# 18F_Proto2.net
KiCad netlist of a schematic drawn in EAGLE
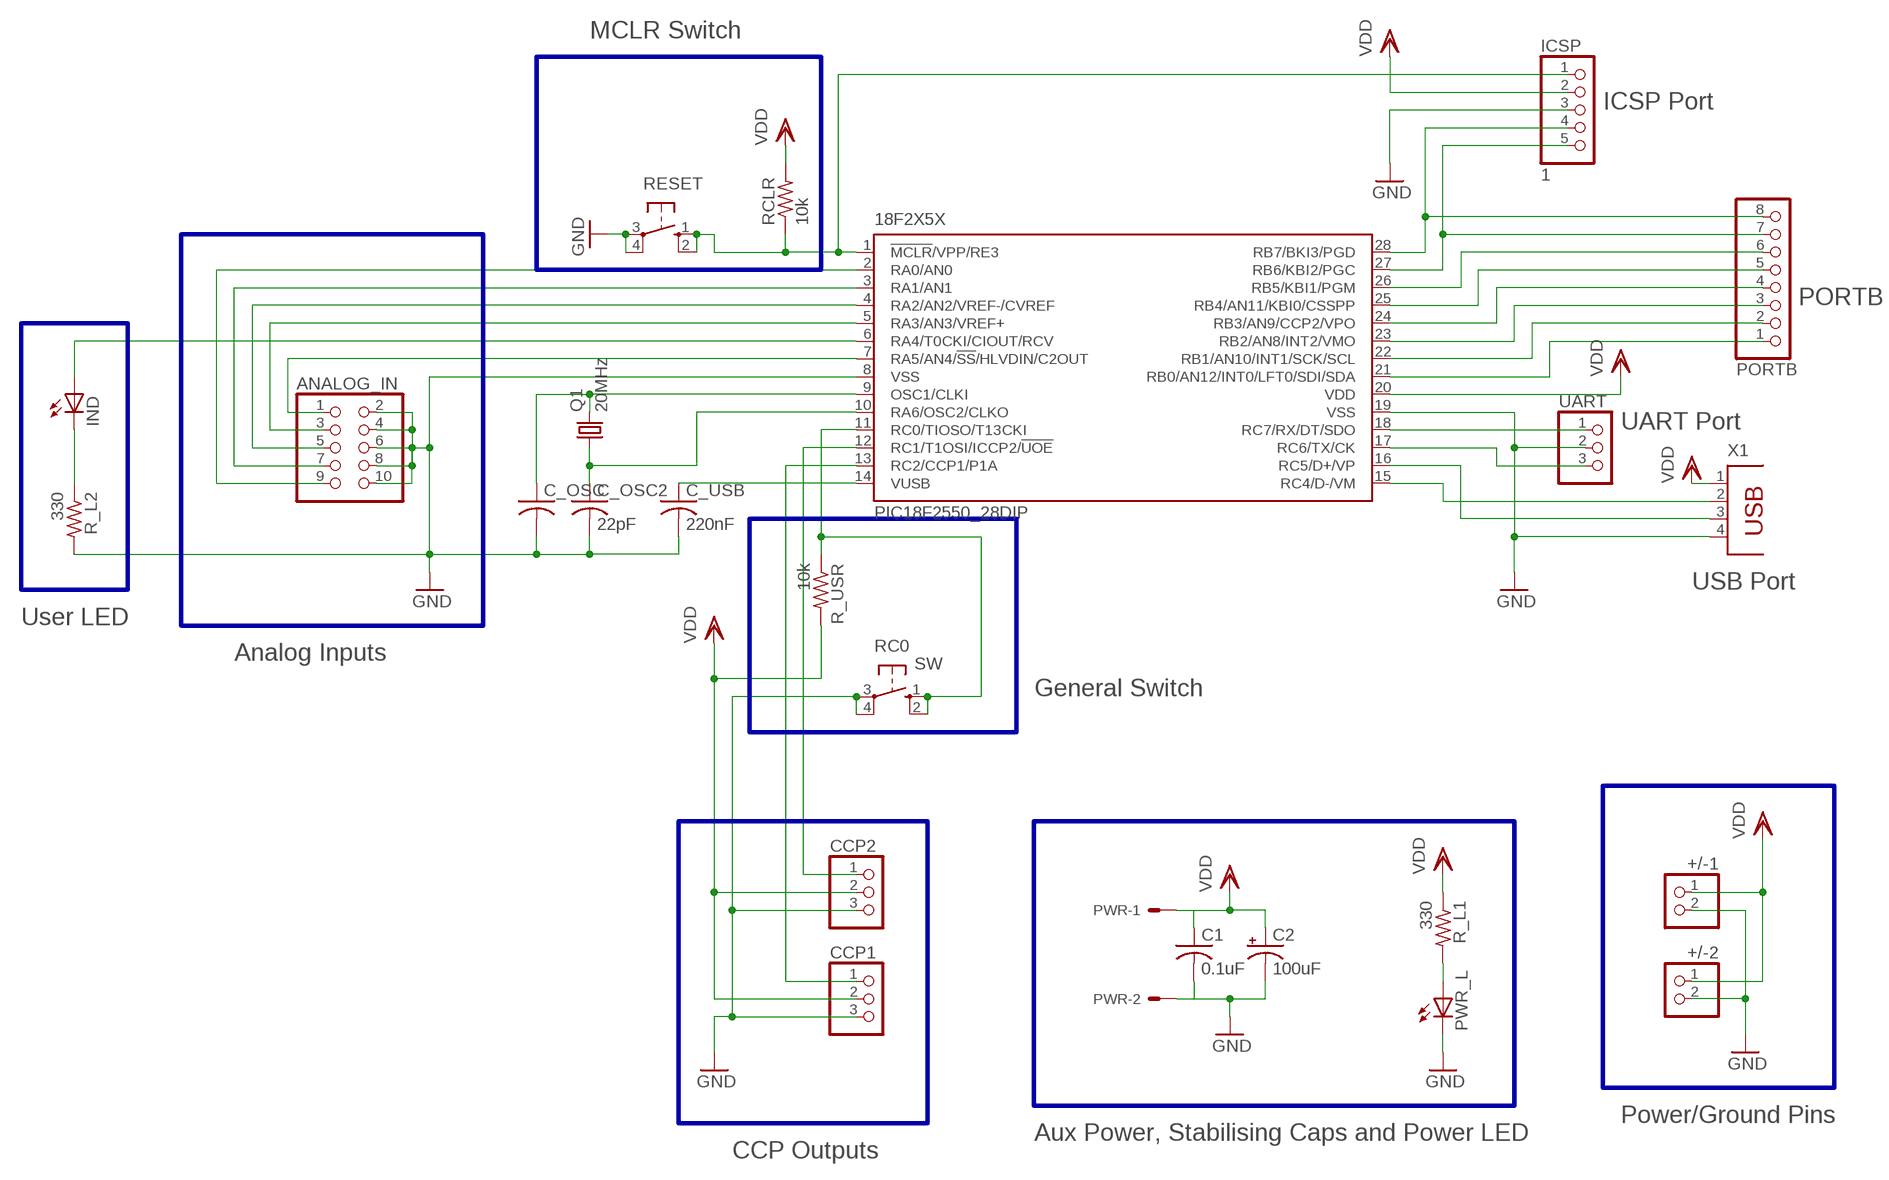
[diagram p0: schematic, sheet 1]

(export (version "E")
  (design (tool "Eeschema 10.0.6"))
  (components
    (comp (ref "+/-1")
      (value "PINHD-1X2")
      (footprint "eagle-import:1X02")
      (libsource (lib "eagle-import") (part "PINHD-1X2"))
    )
    (comp (ref "+/-2")
      (value "PINHD-1X2")
      (footprint "eagle-import:1X02")
      (libsource (lib "eagle-import") (part "PINHD-1X2"))
    )
    (comp (ref "18F2X5X")
      (value "PIC18F2550_28DIP")
      (footprint "eagle-import:DIL28-3")
      (fields (field (name "MF") "MICROCHIP") (field (name "MPN") "PIC18F2550-I/SP"))
      (libsource (lib "eagle-import") (part "PIC18F2_28DIP550"))
    )
    (comp (ref "ANALOG_IN")
      (value "PINHD-2X5")
      (footprint "eagle-import:2X05")
      (libsource (lib "eagle-import") (part "PINHD-2X5"))
    )
    (comp (ref "C1")
      (value "0.1uF")
      (footprint "eagle-import:C050-025X075")
      (libsource (lib "eagle-import") (part "C-US050-025X075"))
    )
    (comp (ref "C2")
      (value "100uF")
      (footprint "eagle-import:E2,5-6")
      (libsource (lib "eagle-import") (part "CPOL-USE2.5-6"))
    )
    (comp (ref "CCP1")
      (value "PINHD-1X3")
      (footprint "eagle-import:1X03")
      (libsource (lib "eagle-import") (part "PINHD-1X3"))
    )
    (comp (ref "CCP2")
      (value "PINHD-1X3")
      (footprint "eagle-import:1X03")
      (libsource (lib "eagle-import") (part "PINHD-1X3"))
    )
    (comp (ref "C_OSC")
      (value "C-US025-025X050")
      (footprint "eagle-import:C025-025X050")
      (libsource (lib "eagle-import") (part "C-US025-025X050"))
    )
    (comp (ref "C_OSC2")
      (value "22pF")
      (footprint "eagle-import:C025-025X050")
      (libsource (lib "eagle-import") (part "C-US025-025X050"))
    )
    (comp (ref "C_USB")
      (value "220nF")
      (footprint "eagle-import:C050-025X075")
      (libsource (lib "eagle-import") (part "C-US050-025X075"))
    )
    (comp (ref "ICSP")
      (value "1")
      (footprint "eagle-import:1X05")
      (libsource (lib "eagle-import") (part "PINHD-1X5"))
    )
    (comp (ref "IND")
      (value "LED3MM")
      (footprint "eagle-import:LED3MM")
      (libsource (lib "eagle-import") (part "LED3MM"))
    )
    (comp (ref "PORTB")
      (value "PINHD-1X8")
      (footprint "eagle-import:1X08")
      (libsource (lib "eagle-import") (part "PINHD-1X8"))
    )
    (comp (ref "PWR")
      (value "22-23-2021")
      (footprint "eagle-import:22-23-2021")
      (fields (field (name "MF") "MOLEX"))
      (libsource (lib "eagle-import") (part "22-23-2021"))
    )
    (comp (ref "PWR_L")
      (value "LED3MM")
      (footprint "eagle-import:LED3MM")
      (libsource (lib "eagle-import") (part "LED3MM"))
    )
    (comp (ref "Q1")
      (value "20MHz")
      (footprint "eagle-import:HC49_S")
      (libsource (lib "eagle-import") (part "CRYSTALHC49S"))
    )
    (comp (ref "RC0")
      (value "SW")
      (footprint "eagle-import:B3F-10XX")
      (fields (field (name "MPN") "B3F-1000"))
      (libsource (lib "eagle-import") (part "10-XX"))
    )
    (comp (ref "RCLR")
      (value "10k")
      (footprint "eagle-import:0204_7")
      (libsource (lib "eagle-import") (part "R-US_0204/7"))
    )
    (comp (ref "RESET")
      (value "10-XX")
      (footprint "eagle-import:B3F-10XX")
      (fields (field (name "MPN") "B3F-1000"))
      (libsource (lib "eagle-import") (part "10-XX"))
    )
    (comp (ref "R_L1")
      (value "330")
      (footprint "eagle-import:0204_7")
      (libsource (lib "eagle-import") (part "R-US_0204/7"))
    )
    (comp (ref "R_L2")
      (value "330")
      (footprint "eagle-import:0207_10")
      (libsource (lib "eagle-import") (part "R-US_0207/10"))
    )
    (comp (ref "R_USR")
      (value "10k")
      (footprint "eagle-import:0204_7")
      (libsource (lib "eagle-import") (part "R-US_0204/7"))
    )
    (comp (ref "UART")
      (value "PINHD-1X3")
      (footprint "eagle-import:1X03")
      (libsource (lib "eagle-import") (part "PINHD-1X3"))
    )
    (comp (ref "X1")
      (value "PN61729")
      (footprint "eagle-import:PN61729")
      (libsource (lib "eagle-import") (part "PN61729"))
    )
  )
  (nets
    (net (code "1") (name "GND") (class "Default")
      (node (ref "+/-1") (pin "2") (pinfunction "2_2") (pintype "passive"))
      (node (ref "+/-2") (pin "2") (pinfunction "2_2") (pintype "passive"))
      (node (ref "18F2X5X") (pin "19") (pinfunction "VSS_19") (pintype "power_in"))
      (node (ref "18F2X5X") (pin "8") (pinfunction "VSS_8") (pintype "power_in"))
      (node (ref "ANALOG_IN") (pin "10") (pinfunction "10_10") (pintype "passive"))
      (node (ref "ANALOG_IN") (pin "2") (pinfunction "2_2") (pintype "passive"))
      (node (ref "ANALOG_IN") (pin "4") (pinfunction "4_4") (pintype "passive"))
      (node (ref "ANALOG_IN") (pin "6") (pinfunction "6_6") (pintype "passive"))
      (node (ref "ANALOG_IN") (pin "8") (pinfunction "8_8") (pintype "passive"))
      (node (ref "C1") (pin "2") (pinfunction "2_2") (pintype "passive"))
      (node (ref "C2") (pin "-") (pinfunction "-_-") (pintype "passive"))
      (node (ref "CCP1") (pin "3") (pinfunction "3_3") (pintype "passive"))
      (node (ref "CCP2") (pin "3") (pinfunction "3_3") (pintype "passive"))
      (node (ref "C_OSC") (pin "2") (pinfunction "2_2") (pintype "passive"))
      (node (ref "C_OSC2") (pin "2") (pinfunction "2_2") (pintype "passive"))
      (node (ref "C_USB") (pin "2") (pinfunction "2_2") (pintype "passive"))
      (node (ref "ICSP") (pin "3") (pinfunction "3_3") (pintype "passive"))
      (node (ref "PWR") (pin "2") (pinfunction "S_2") (pintype "passive"))
      (node (ref "PWR_L") (pin "K") (pinfunction "C_K") (pintype "passive"))
      (node (ref "RC0") (pin "3") (pinfunction "P_3") (pintype "passive"))
      (node (ref "RC0") (pin "4") (pinfunction "P1_4") (pintype "passive"))
      (node (ref "RESET") (pin "3") (pinfunction "P_3") (pintype "passive"))
      (node (ref "RESET") (pin "4") (pinfunction "P1_4") (pintype "passive"))
      (node (ref "R_L2") (pin "2") (pinfunction "2_2") (pintype "passive"))
      (node (ref "UART") (pin "2") (pinfunction "2_2") (pintype "passive"))
      (node (ref "X1") (pin "4") (pinfunction "4_4") (pintype "passive"))
    )
    (net (code "2") (name "Net-(18F2X5X-OSC1{slash}CLKI)") (class "Default")
      (node (ref "18F2X5X") (pin "9") (pinfunction "OSC1/CLKI_9") (pintype "input"))
      (node (ref "C_OSC") (pin "1") (pinfunction "1_1") (pintype "passive"))
      (node (ref "Q1") (pin "2") (pinfunction "2_2") (pintype "passive"))
    )
    (net (code "3") (name "Net-(18F2X5X-RA0{slash}AN0)") (class "Default")
      (node (ref "18F2X5X") (pin "2") (pinfunction "RA0/AN0_2") (pintype "bidirectional"))
      (node (ref "ANALOG_IN") (pin "9") (pinfunction "9_9") (pintype "passive"))
    )
    (net (code "4") (name "Net-(18F2X5X-RA1{slash}AN1)") (class "Default")
      (node (ref "18F2X5X") (pin "3") (pinfunction "RA1/AN1_3") (pintype "bidirectional"))
      (node (ref "ANALOG_IN") (pin "7") (pinfunction "7_7") (pintype "passive"))
    )
    (net (code "5") (name "Net-(18F2X5X-RA2{slash}AN2{slash}VREF-{slash}CVREF)") (class "Default")
      (node (ref "18F2X5X") (pin "4") (pinfunction "RA2/AN2/VREF-/CVREF_4") (pintype "bidirectional"))
      (node (ref "ANALOG_IN") (pin "5") (pinfunction "5_5") (pintype "passive"))
    )
    (net (code "6") (name "Net-(18F2X5X-RA3{slash}AN3{slash}VREF+)") (class "Default")
      (node (ref "18F2X5X") (pin "5") (pinfunction "RA3/AN3/VREF+_5") (pintype "bidirectional"))
      (node (ref "ANALOG_IN") (pin "3") (pinfunction "3_3") (pintype "passive"))
    )
    (net (code "7") (name "Net-(18F2X5X-RA4{slash}T0CKI{slash}CIOUT{slash}RCV)") (class "Default")
      (node (ref "18F2X5X") (pin "6") (pinfunction "RA4/T0CKI/CIOUT/RCV_6") (pintype "bidirectional"))
      (node (ref "IND") (pin "A") (pinfunction "A_A") (pintype "passive"))
    )
    (net (code "8") (name "Net-(18F2X5X-RA5{slash}AN4{slash}~{SS}{slash}HLVDIN{slash}C2OUT)") (class "Default")
      (node (ref "18F2X5X") (pin "7") (pinfunction "RA5/AN4/~{SS}/HLVDIN/C2OUT_7") (pintype "bidirectional"))
      (node (ref "ANALOG_IN") (pin "1") (pinfunction "1_1") (pintype "passive"))
    )
    (net (code "9") (name "Net-(18F2X5X-RA6{slash}OSC2{slash}CLKO)") (class "Default")
      (node (ref "18F2X5X") (pin "10") (pinfunction "RA6/OSC2/CLKO_10") (pintype "output"))
      (node (ref "C_OSC2") (pin "1") (pinfunction "1_1") (pintype "passive"))
      (node (ref "Q1") (pin "1") (pinfunction "1_1") (pintype "passive"))
    )
    (net (code "10") (name "Net-(18F2X5X-RB0{slash}AN12{slash}INT0{slash}LFT0{slash}SDI{slash}SDA)") (class "Default")
      (node (ref "18F2X5X") (pin "21") (pinfunction "RB0/AN12/INT0/LFT0/SDI/SDA_21") (pintype "bidirectional"))
      (node (ref "PORTB") (pin "1") (pinfunction "1_1") (pintype "passive"))
    )
    (net (code "11") (name "Net-(18F2X5X-RB1{slash}AN10{slash}INT1{slash}SCK{slash}SCL)") (class "Default")
      (node (ref "18F2X5X") (pin "22") (pinfunction "RB1/AN10/INT1/SCK/SCL_22") (pintype "bidirectional"))
      (node (ref "PORTB") (pin "2") (pinfunction "2_2") (pintype "passive"))
    )
    (net (code "12") (name "Net-(18F2X5X-RB2{slash}AN8{slash}INT2{slash}VMO)") (class "Default")
      (node (ref "18F2X5X") (pin "23") (pinfunction "RB2/AN8/INT2/VMO_23") (pintype "bidirectional"))
      (node (ref "PORTB") (pin "3") (pinfunction "3_3") (pintype "passive"))
    )
    (net (code "13") (name "Net-(18F2X5X-RB3{slash}AN9{slash}CCP2{slash}VPO)") (class "Default")
      (node (ref "18F2X5X") (pin "24") (pinfunction "RB3/AN9/CCP2/VPO_24") (pintype "bidirectional"))
      (node (ref "PORTB") (pin "4") (pinfunction "4_4") (pintype "passive"))
    )
    (net (code "14") (name "Net-(18F2X5X-RB4{slash}AN11{slash}KBI0{slash}CSSPP)") (class "Default")
      (node (ref "18F2X5X") (pin "25") (pinfunction "RB4/AN11/KBI0/CSSPP_25") (pintype "bidirectional"))
      (node (ref "PORTB") (pin "5") (pinfunction "5_5") (pintype "passive"))
    )
    (net (code "15") (name "Net-(18F2X5X-RB5{slash}KBI1{slash}PGM)") (class "Default")
      (node (ref "18F2X5X") (pin "26") (pinfunction "RB5/KBI1/PGM_26") (pintype "bidirectional"))
      (node (ref "PORTB") (pin "6") (pinfunction "6_6") (pintype "passive"))
    )
    (net (code "16") (name "Net-(18F2X5X-RB6{slash}KBI2{slash}PGC)") (class "Default")
      (node (ref "18F2X5X") (pin "27") (pinfunction "RB6/KBI2/PGC_27") (pintype "bidirectional"))
      (node (ref "ICSP") (pin "5") (pinfunction "5_5") (pintype "passive"))
      (node (ref "PORTB") (pin "7") (pinfunction "7_7") (pintype "passive"))
    )
    (net (code "17") (name "Net-(18F2X5X-RB7{slash}BKI3{slash}PGD)") (class "Default")
      (node (ref "18F2X5X") (pin "28") (pinfunction "RB7/BKI3/PGD_28") (pintype "bidirectional"))
      (node (ref "ICSP") (pin "4") (pinfunction "4_4") (pintype "passive"))
      (node (ref "PORTB") (pin "8") (pinfunction "8_8") (pintype "passive"))
    )
    (net (code "18") (name "Net-(18F2X5X-RC0{slash}TIOSO{slash}T13CKI)") (class "Default")
      (node (ref "18F2X5X") (pin "11") (pinfunction "RC0/TIOSO/T13CKI_11") (pintype "bidirectional"))
      (node (ref "RC0") (pin "1") (pinfunction "S_1") (pintype "passive"))
      (node (ref "RC0") (pin "2") (pinfunction "S1_2") (pintype "passive"))
      (node (ref "R_USR") (pin "1") (pinfunction "1_1") (pintype "passive"))
    )
    (net (code "19") (name "Net-(18F2X5X-RC1{slash}T1OSI{slash}ICCP2{slash}~{UOE})") (class "Default")
      (node (ref "18F2X5X") (pin "12") (pinfunction "RC1/T1OSI/ICCP2/~{UOE}_12") (pintype "bidirectional"))
      (node (ref "CCP2") (pin "1") (pinfunction "1_1") (pintype "passive"))
    )
    (net (code "20") (name "Net-(18F2X5X-RC2{slash}CCP1{slash}P1A)") (class "Default")
      (node (ref "18F2X5X") (pin "13") (pinfunction "RC2/CCP1/P1A_13") (pintype "bidirectional"))
      (node (ref "CCP1") (pin "1") (pinfunction "1_1") (pintype "passive"))
    )
    (net (code "21") (name "Net-(18F2X5X-RC4{slash}D-{slash}VM)") (class "Default")
      (node (ref "18F2X5X") (pin "15") (pinfunction "RC4/D-/VM_15") (pintype "bidirectional"))
      (node (ref "X1") (pin "2") (pinfunction "2_2") (pintype "passive"))
    )
    (net (code "22") (name "Net-(18F2X5X-RC5{slash}D+{slash}VP)") (class "Default")
      (node (ref "18F2X5X") (pin "16") (pinfunction "RC5/D+/VP_16") (pintype "bidirectional"))
      (node (ref "X1") (pin "3") (pinfunction "3_3") (pintype "passive"))
    )
    (net (code "23") (name "Net-(18F2X5X-RC6{slash}TX{slash}CK)") (class "Default")
      (node (ref "18F2X5X") (pin "17") (pinfunction "RC6/TX/CK_17") (pintype "bidirectional"))
      (node (ref "UART") (pin "3") (pinfunction "3_3") (pintype "passive"))
    )
    (net (code "24") (name "Net-(18F2X5X-RC7{slash}RX{slash}DT{slash}SDO)") (class "Default")
      (node (ref "18F2X5X") (pin "18") (pinfunction "RC7/RX/DT/SDO_18") (pintype "bidirectional"))
      (node (ref "UART") (pin "1") (pinfunction "1_1") (pintype "passive"))
    )
    (net (code "25") (name "Net-(18F2X5X-VUSB)") (class "Default")
      (node (ref "18F2X5X") (pin "14") (pinfunction "VUSB_14") (pintype "bidirectional"))
      (node (ref "C_USB") (pin "1") (pinfunction "1_1") (pintype "passive"))
    )
    (net (code "26") (name "Net-(18F2X5X-~{MCLR}{slash}VPP{slash}RE3)") (class "Default")
      (node (ref "18F2X5X") (pin "1") (pinfunction "~{MCLR}/VPP/RE3_1") (pintype "input"))
      (node (ref "ICSP") (pin "1") (pinfunction "1_1") (pintype "passive"))
      (node (ref "RCLR") (pin "1") (pinfunction "1_1") (pintype "passive"))
      (node (ref "RESET") (pin "1") (pinfunction "S_1") (pintype "passive"))
      (node (ref "RESET") (pin "2") (pinfunction "S1_2") (pintype "passive"))
    )
    (net (code "27") (name "Net-(IND-C)") (class "Default")
      (node (ref "IND") (pin "K") (pinfunction "C_K") (pintype "passive"))
      (node (ref "R_L2") (pin "1") (pinfunction "1_1") (pintype "passive"))
    )
    (net (code "28") (name "Net-(PWR_L-PadA)") (class "Default")
      (node (ref "PWR_L") (pin "A") (pinfunction "A_A") (pintype "passive"))
      (node (ref "R_L1") (pin "2") (pinfunction "2_2") (pintype "passive"))
    )
    (net (code "29") (name "VDD") (class "Default")
      (node (ref "+/-1") (pin "1") (pinfunction "1_1") (pintype "passive"))
      (node (ref "+/-2") (pin "1") (pinfunction "1_1") (pintype "passive"))
      (node (ref "18F2X5X") (pin "20") (pinfunction "VDD_20") (pintype "power_in"))
      (node (ref "C1") (pin "1") (pinfunction "1_1") (pintype "passive"))
      (node (ref "C2") (pin "+") (pinfunction "+_+") (pintype "passive"))
      (node (ref "CCP1") (pin "2") (pinfunction "2_2") (pintype "passive"))
      (node (ref "CCP2") (pin "2") (pinfunction "2_2") (pintype "passive"))
      (node (ref "ICSP") (pin "2") (pinfunction "2_2") (pintype "passive"))
      (node (ref "PWR") (pin "1") (pinfunction "S_1") (pintype "passive"))
      (node (ref "RCLR") (pin "2") (pinfunction "2_2") (pintype "passive"))
      (node (ref "R_L1") (pin "1") (pinfunction "1_1") (pintype "passive"))
      (node (ref "R_USR") (pin "2") (pinfunction "2_2") (pintype "passive"))
      (node (ref "X1") (pin "1") (pinfunction "1_1") (pintype "passive"))
    )
  )
)
